# MCU.net
KiCad netlist of a schematic drawn in Altium Designer
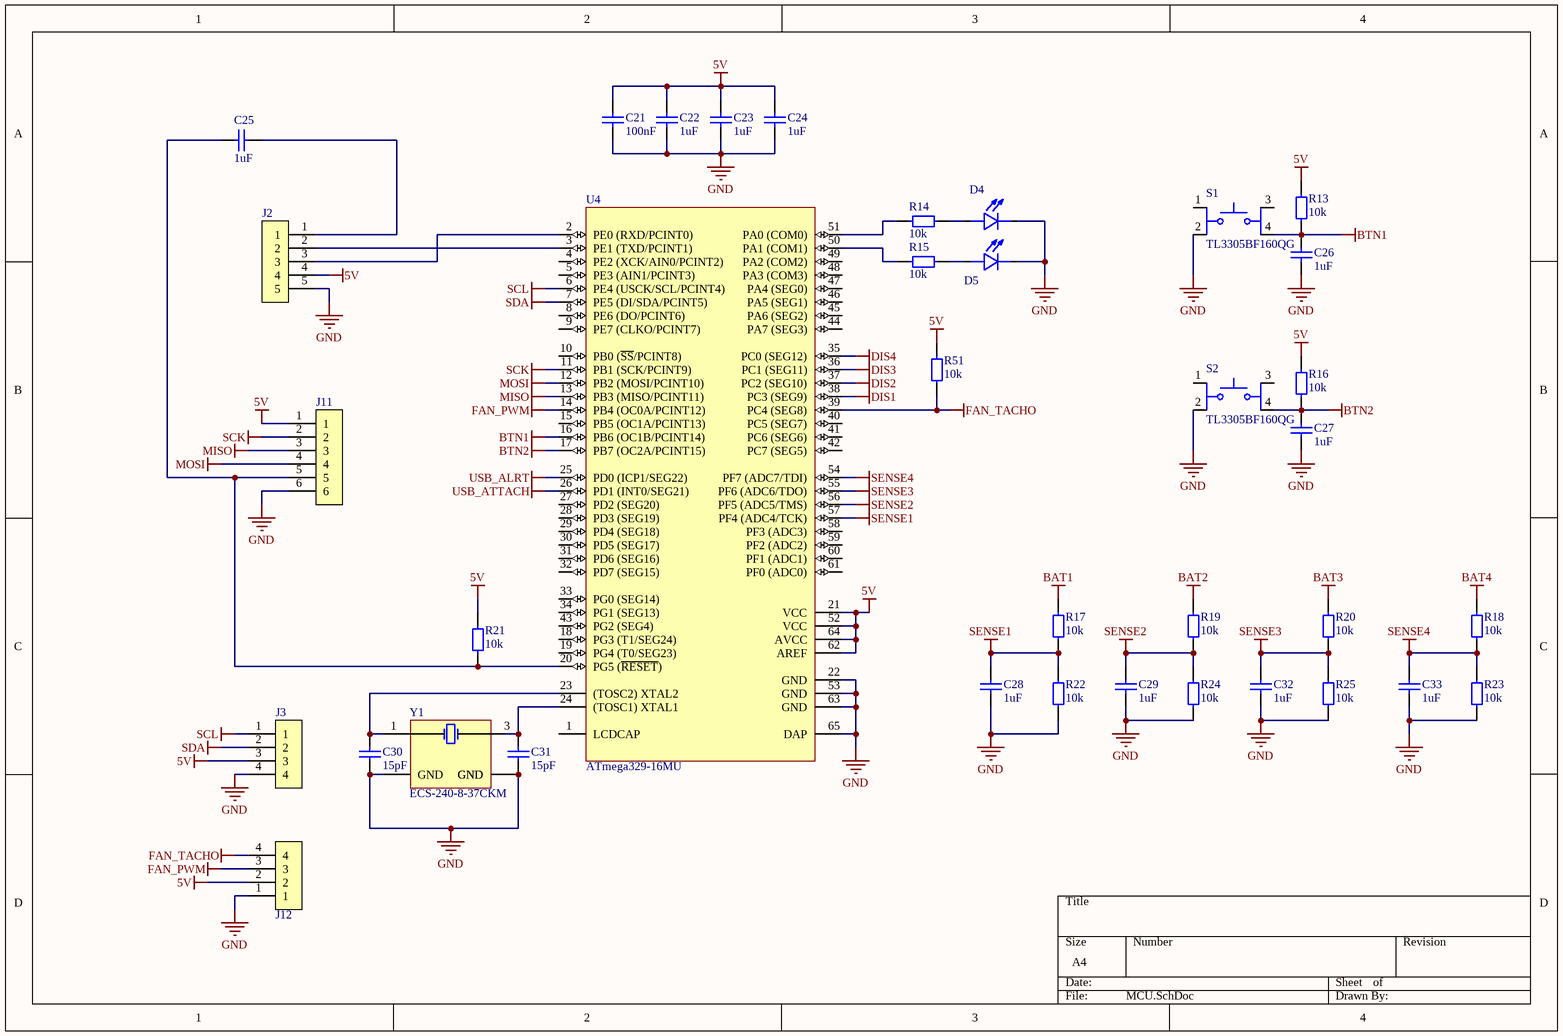
[diagram p0: MCU.SchDoc]

(export (version "E")
  (design (tool "Eeschema 10.0.6"))
  (components
    (comp (ref "C21")
      (value "100nF")
      (footprint "0603 Capacitor")
      (description "100nF 50V 0603")
      (libsource (lib "Capacitor") (part "Capacitor 100nF 0603"))
    )
    (comp (ref "C22")
      (value "1uF")
      (footprint "0603 Capacitor")
      (description "1uF 50V 0603")
      (libsource (lib "Capacitor") (part "Capacitor 1uF 0603"))
    )
    (comp (ref "C23")
      (value "1uF")
      (footprint "0603 Capacitor")
      (description "1uF 50V 0603")
      (libsource (lib "Capacitor") (part "Capacitor 1uF 0603"))
    )
    (comp (ref "C24")
      (value "1uF")
      (footprint "0603 Capacitor")
      (description "1uF 50V 0603")
      (libsource (lib "Capacitor") (part "Capacitor 1uF 0603"))
    )
    (comp (ref "C25")
      (value "1uF")
      (footprint "0603 Capacitor")
      (description "1uF 50V 0603")
      (libsource (lib "Capacitor") (part "Capacitor 1uF 0603"))
    )
    (comp (ref "C26")
      (value "1uF")
      (footprint "0603 Capacitor")
      (description "1uF 50V 0603")
      (libsource (lib "Capacitor") (part "Capacitor 1uF 0603"))
    )
    (comp (ref "C27")
      (value "1uF")
      (footprint "0603 Capacitor")
      (description "1uF 50V 0603")
      (libsource (lib "Capacitor") (part "Capacitor 1uF 0603"))
    )
    (comp (ref "C28")
      (value "1uF")
      (footprint "0603 Capacitor")
      (description "1uF 50V 0603")
      (libsource (lib "Capacitor") (part "Capacitor 1uF 0603"))
    )
    (comp (ref "C29")
      (value "1uF")
      (footprint "0603 Capacitor")
      (description "1uF 50V 0603")
      (libsource (lib "Capacitor") (part "Capacitor 1uF 0603"))
    )
    (comp (ref "C30")
      (value "15pF")
      (footprint "0603 Capacitor")
      (description "15pF 50V 0603")
      (fields (field (name "MP") "KAM15AR71H103MT"))
      (libsource (lib "Capacitor") (part "Capacitor 15pF 0603"))
    )
    (comp (ref "C31")
      (value "15pF")
      (footprint "0603 Capacitor")
      (description "15pF 50V 0603")
      (fields (field (name "MP") "KAM15AR71H103MT"))
      (libsource (lib "Capacitor") (part "Capacitor 15pF 0603"))
    )
    (comp (ref "C32")
      (value "1uF")
      (footprint "0603 Capacitor")
      (description "1uF 50V 0603")
      (libsource (lib "Capacitor") (part "Capacitor 1uF 0603"))
    )
    (comp (ref "C33")
      (value "1uF")
      (footprint "0603 Capacitor")
      (description "1uF 50V 0603")
      (libsource (lib "Capacitor") (part "Capacitor 1uF 0603"))
    )
    (comp (ref "D4")
      (value "LTST-C190KGKT")
      (footprint "LED 0603")
      (description "1.6x0.8mm Smd Chip Led Lamp")
      (fields (field (name "MF") "Kingbright") (field (name "MP") "KPT-1608ZGC"))
      (libsource (lib "LED") (part "LED 0603"))
    )
    (comp (ref "D5")
      (value "LTST-C190KGKT")
      (footprint "LED 0603")
      (description "1.6x0.8mm Smd Chip Led Lamp")
      (fields (field (name "MF") "Kingbright") (field (name "MP") "KPT-1608ZGC"))
      (libsource (lib "LED") (part "LED 0603"))
    )
    (comp (ref "J2")
      (value "5-534237-3")
      (footprint "5pin header")
      (description "2.54mm")
      (fields (field (name "MF") "{'manufacturer': 'TE Connectivity'}") (field (name "MP") "534237-4"))
      (libsource (lib "Connector") (part "5pin 2.54 SAMTEC"))
    )
    (comp (ref "J3")
      (value "MTSW-104-07-G-S-000")
      (footprint "HDRV4W64P0X254_1X4_1016X254X864P")
      (description "CONN HEADER VERT 4POS 2.54MM")
      (libsource (lib "") (part "4 pin header_1"))
    )
    (comp (ref "J11")
      (value "MTSW-106-07-L-S-210")
      (footprint "SAMTEC_MTSW-106-23-L-S-240")
      (description "CONN HEADER VERT 6POS 2.54MM")
      (fields
        (field (name "MANUFACTURER_PART_NUMBER") "MTSW-104-07-G-S-000")
        (field (name "MP") "4 pin header")
      )
      (libsource (lib "Connector") (part "6 pin header"))
    )
    (comp (ref "J12")
      (value "MTSW-104-07-G-S-000")
      (footprint "HDRV4W64P0X254_1X4_1016X254X864P")
      (description "CONN HEADER VERT 4POS 2.54MM")
      (fields (field (name "MP") "4 pin header"))
      (libsource (lib "Connector") (part "4 pin header"))
    )
    (comp (ref "R13")
      (value "10k")
      (footprint "0603 Resistor")
      (description "10k 0603")
      (libsource (lib "Resistors") (part "Resistor 10k 0603"))
    )
    (comp (ref "R14")
      (value "10k")
      (footprint "0603 Resistor")
      (description "10k 0603")
      (libsource (lib "Resistors") (part "Resistor 10k 0603"))
    )
    (comp (ref "R15")
      (value "10k")
      (footprint "0603 Resistor")
      (description "10k 0603")
      (libsource (lib "Resistors") (part "Resistor 10k 0603"))
    )
    (comp (ref "R16")
      (value "10k")
      (footprint "0603 Resistor")
      (description "10k 0603")
      (libsource (lib "Resistors") (part "Resistor 10k 0603"))
    )
    (comp (ref "R17")
      (value "10k")
      (footprint "0603 Resistor")
      (description "10k 0603")
      (libsource (lib "Resistors") (part "Resistor 10k 0603"))
    )
    (comp (ref "R18")
      (value "10k")
      (footprint "0603 Resistor")
      (description "10k 0603")
      (libsource (lib "Resistors") (part "Resistor 10k 0603"))
    )
    (comp (ref "R19")
      (value "10k")
      (footprint "0603 Resistor")
      (description "10k 0603")
      (libsource (lib "Resistors") (part "Resistor 10k 0603"))
    )
    (comp (ref "R20")
      (value "10k")
      (footprint "0603 Resistor")
      (description "10k 0603")
      (libsource (lib "Resistors") (part "Resistor 10k 0603"))
    )
    (comp (ref "R21")
      (value "10k")
      (footprint "0603 Resistor")
      (description "10k 0603")
      (libsource (lib "Resistors") (part "Resistor 10k 0603"))
    )
    (comp (ref "R22")
      (value "10k")
      (footprint "0603 Resistor")
      (description "10k 0603")
      (libsource (lib "Resistors") (part "Resistor 10k 0603"))
    )
    (comp (ref "R23")
      (value "10k")
      (footprint "0603 Resistor")
      (description "10k 0603")
      (libsource (lib "Resistors") (part "Resistor 10k 0603"))
    )
    (comp (ref "R24")
      (value "10k")
      (footprint "0603 Resistor")
      (description "10k 0603")
      (libsource (lib "Resistors") (part "Resistor 10k 0603"))
    )
    (comp (ref "R25")
      (value "10k")
      (footprint "0603 Resistor")
      (description "10k 0603")
      (libsource (lib "Resistors") (part "Resistor 10k 0603"))
    )
    (comp (ref "R51")
      (value "10k")
      (footprint "0603 Resistor")
      (description "10k 0603")
      (libsource (lib "Resistors") (part "Resistor 10k 0603"))
    )
    (comp (ref "S1")
      (value "TL3305BF160QG")
      (footprint "SW_TL3305BF160QG")
      (description "Tactile Switch SPST-NO Top Actuated Surface Mount")
      (fields (field (name "MF") "E-Switch"))
      (libsource (lib "Switches") (part "TL3305BF160QG"))
    )
    (comp (ref "S2")
      (value "TL3305BF160QG")
      (footprint "SW_TL3305BF160QG")
      (description "Tactile Switch SPST-NO Top Actuated Surface Mount")
      (fields (field (name "MF") "E-Switch"))
      (libsource (lib "Switches") (part "TL3305BF160QG"))
    )
    (comp (ref "U4")
      (value "ATmega329-16MU")
      (footprint "ATmega329")
      (libsource (lib "DCDC") (part "ATmega329-16MU"))
    )
    (comp (ref "Y1")
      (value "ECS-240-8-37CKM")
      (footprint "IC:XTAL_ECS-240-8-37CKM")
      (libsource (lib "Crystal") (part "ECS-240-8-37CKM"))
    )
  )
  (nets
    (net (code "1") (name "5V") (class "Default")
      (node (ref "C21") (pin "2") (pinfunction "2_2") (pintype "passive"))
      (node (ref "C22") (pin "2") (pinfunction "2_2") (pintype "passive"))
      (node (ref "C23") (pin "2") (pinfunction "2_2") (pintype "passive"))
      (node (ref "C24") (pin "2") (pinfunction "2_2") (pintype "passive"))
      (node (ref "J11") (pin "1") (pinfunction "1_1") (pintype "passive"))
      (node (ref "J12") (pin "2") (pinfunction "2_2") (pintype "passive"))
      (node (ref "J2") (pin "4") (pinfunction "4_4") (pintype "passive"))
      (node (ref "J3") (pin "3") (pinfunction "3_3") (pintype "passive"))
      (node (ref "R13") (pin "1") (pinfunction "CCW_1") (pintype "passive"))
      (node (ref "R16") (pin "1") (pinfunction "CCW_1") (pintype "passive"))
      (node (ref "R21") (pin "1") (pinfunction "CCW_1") (pintype "passive"))
      (node (ref "R51") (pin "2") (pinfunction "CW_2") (pintype "passive"))
      (node (ref "U4") (pin "21") (pinfunction "VCC_21") (pintype "power_in"))
      (node (ref "U4") (pin "52") (pinfunction "VCC_52") (pintype "power_in"))
      (node (ref "U4") (pin "62") (pinfunction "AREF_62") (pintype "passive"))
      (node (ref "U4") (pin "64") (pinfunction "AVCC_64") (pintype "power_in"))
    )
    (net (code "2") (name "BAT1") (class "Default")
      (node (ref "R17") (pin "1") (pinfunction "CCW_1") (pintype "passive"))
    )
    (net (code "3") (name "BAT2") (class "Default")
      (node (ref "R19") (pin "1") (pinfunction "CCW_1") (pintype "passive"))
    )
    (net (code "4") (name "BAT3") (class "Default")
      (node (ref "R20") (pin "1") (pinfunction "CCW_1") (pintype "passive"))
    )
    (net (code "5") (name "BAT4") (class "Default")
      (node (ref "R18") (pin "1") (pinfunction "CCW_1") (pintype "passive"))
    )
    (net (code "6") (name "BTN1") (class "Default")
      (node (ref "C26") (pin "2") (pinfunction "2_2") (pintype "passive"))
      (node (ref "R13") (pin "2") (pinfunction "CW_2") (pintype "passive"))
      (node (ref "S1") (pin "4") (pinfunction "4_4") (pintype "passive"))
      (node (ref "U4") (pin "16") (pinfunction "PB6_(OC1B/PCINT14)_16") (pintype "bidirectional"))
    )
    (net (code "7") (name "BTN2") (class "Default")
      (node (ref "C27") (pin "2") (pinfunction "2_2") (pintype "passive"))
      (node (ref "R16") (pin "2") (pinfunction "CW_2") (pintype "passive"))
      (node (ref "S2") (pin "4") (pinfunction "4_4") (pintype "passive"))
      (node (ref "U4") (pin "17") (pinfunction "PB7_(OC2A/PCINT15)_17") (pintype "bidirectional"))
    )
    (net (code "8") (name "DIS1") (class "Default")
      (node (ref "U4") (pin "38") (pinfunction "PC3_(SEG9)_38") (pintype "bidirectional"))
    )
    (net (code "9") (name "DIS2") (class "Default")
      (node (ref "U4") (pin "37") (pinfunction "PC2_(SEG10)_37") (pintype "bidirectional"))
    )
    (net (code "10") (name "DIS3") (class "Default")
      (node (ref "U4") (pin "36") (pinfunction "PC1_(SEG11)_36") (pintype "bidirectional"))
    )
    (net (code "11") (name "DIS4") (class "Default")
      (node (ref "U4") (pin "35") (pinfunction "PC0_(SEG12)_35") (pintype "bidirectional"))
    )
    (net (code "12") (name "FAN_PWM") (class "Default")
      (node (ref "J12") (pin "3") (pinfunction "3_3") (pintype "passive"))
      (node (ref "U4") (pin "14") (pinfunction "PB4_(OC0A/PCINT12)_14") (pintype "bidirectional"))
    )
    (net (code "13") (name "FAN_TACHO") (class "Default")
      (node (ref "J12") (pin "4") (pinfunction "4_4") (pintype "passive"))
      (node (ref "R51") (pin "1") (pinfunction "CCW_1") (pintype "passive"))
      (node (ref "U4") (pin "39") (pinfunction "PC4_(SEG8)_39") (pintype "bidirectional"))
    )
    (net (code "14") (name "GND") (class "Default")
      (node (ref "C21") (pin "1") (pinfunction "1_1") (pintype "passive"))
      (node (ref "C22") (pin "1") (pinfunction "1_1") (pintype "passive"))
      (node (ref "C23") (pin "1") (pinfunction "1_1") (pintype "passive"))
      (node (ref "C24") (pin "1") (pinfunction "1_1") (pintype "passive"))
      (node (ref "C26") (pin "1") (pinfunction "1_1") (pintype "passive"))
      (node (ref "C27") (pin "1") (pinfunction "1_1") (pintype "passive"))
      (node (ref "C28") (pin "1") (pinfunction "1_1") (pintype "passive"))
      (node (ref "C29") (pin "1") (pinfunction "1_1") (pintype "passive"))
      (node (ref "C30") (pin "1") (pinfunction "1_1") (pintype "passive"))
      (node (ref "C31") (pin "1") (pinfunction "1_1") (pintype "passive"))
      (node (ref "C32") (pin "1") (pinfunction "1_1") (pintype "passive"))
      (node (ref "C33") (pin "1") (pinfunction "1_1") (pintype "passive"))
      (node (ref "D4") (pin "2") (pinfunction "C_2") (pintype "passive"))
      (node (ref "D5") (pin "2") (pinfunction "C_2") (pintype "passive"))
      (node (ref "J11") (pin "6") (pinfunction "6_6") (pintype "passive"))
      (node (ref "J12") (pin "1") (pinfunction "1_1") (pintype "passive"))
      (node (ref "J2") (pin "5") (pinfunction "5_5") (pintype "passive"))
      (node (ref "J3") (pin "4") (pinfunction "4_4") (pintype "passive"))
      (node (ref "R22") (pin "2") (pinfunction "CW_2") (pintype "passive"))
      (node (ref "R23") (pin "2") (pinfunction "CW_2") (pintype "passive"))
      (node (ref "R24") (pin "2") (pinfunction "CW_2") (pintype "passive"))
      (node (ref "R25") (pin "2") (pinfunction "CW_2") (pintype "passive"))
      (node (ref "S1") (pin "2") (pinfunction "2_2") (pintype "passive"))
      (node (ref "S2") (pin "2") (pinfunction "2_2") (pintype "passive"))
      (node (ref "U4") (pin "22") (pinfunction "GND_22") (pintype "power_in"))
      (node (ref "U4") (pin "53") (pinfunction "GND_53") (pintype "power_in"))
      (node (ref "U4") (pin "63") (pinfunction "GND_63") (pintype "power_in"))
      (node (ref "U4") (pin "65") (pinfunction "DAP_65") (pintype "power_in"))
      (node (ref "Y1") (pin "2") (pinfunction "GND_2") (pintype "passive"))
      (node (ref "Y1") (pin "4") (pinfunction "GND_4") (pintype "passive"))
    )
    (net (code "15") (name "MISO") (class "Default")
      (node (ref "J11") (pin "3") (pinfunction "3_3") (pintype "passive"))
      (node (ref "U4") (pin "13") (pinfunction "PB3_(MISO/PCINT11)_13") (pintype "bidirectional"))
    )
    (net (code "16") (name "MOSI") (class "Default")
      (node (ref "J11") (pin "4") (pinfunction "4_4") (pintype "passive"))
      (node (ref "U4") (pin "12") (pinfunction "PB2_(MOSI/PCINT10)_12") (pintype "bidirectional"))
    )
    (net (code "17") (name "Net-(C25-Pad1)") (class "Default")
      (node (ref "C25") (pin "1") (pinfunction "1_1") (pintype "passive"))
      (node (ref "J2") (pin "1") (pinfunction "1_1") (pintype "passive"))
    )
    (net (code "18") (name "Net-(D4-A)") (class "Default")
      (node (ref "D4") (pin "1") (pinfunction "A_1") (pintype "passive"))
      (node (ref "R14") (pin "1") (pinfunction "CCW_1") (pintype "passive"))
    )
    (net (code "19") (name "Net-(D5-A)") (class "Default")
      (node (ref "D5") (pin "1") (pinfunction "A_1") (pintype "passive"))
      (node (ref "R15") (pin "1") (pinfunction "CCW_1") (pintype "passive"))
    )
    (net (code "20") (name "Net-(R14-CW)") (class "Default")
      (node (ref "R14") (pin "2") (pinfunction "CW_2") (pintype "passive"))
      (node (ref "U4") (pin "51") (pinfunction "PA0_(COM0)_51") (pintype "bidirectional"))
    )
    (net (code "21") (name "Net-(R15-CW)") (class "Default")
      (node (ref "R15") (pin "2") (pinfunction "CW_2") (pintype "passive"))
      (node (ref "U4") (pin "50") (pinfunction "PA1_(COM1)_50") (pintype "bidirectional"))
    )
    (net (code "22") (name "Net-(R21-CW)") (class "Default")
      (node (ref "C25") (pin "2") (pinfunction "2_2") (pintype "passive"))
      (node (ref "J11") (pin "5") (pinfunction "5_5") (pintype "passive"))
      (node (ref "R21") (pin "2") (pinfunction "CW_2") (pintype "passive"))
      (node (ref "U4") (pin "20") (pinfunction "PG5_(~{RESET})_20") (pintype "bidirectional"))
    )
    (net (code "23") (name "Net-(U4-(TOSC1)_XTAL1)") (class "Default")
      (node (ref "C31") (pin "2") (pinfunction "2_2") (pintype "passive"))
      (node (ref "U4") (pin "24") (pinfunction "(TOSC1)_XTAL1_24") (pintype "passive"))
      (node (ref "Y1") (pin "3") (pinfunction "X2_3") (pintype "passive"))
    )
    (net (code "24") (name "Net-(U4-(TOSC2)_XTAL2)") (class "Default")
      (node (ref "C30") (pin "2") (pinfunction "2_2") (pintype "passive"))
      (node (ref "U4") (pin "23") (pinfunction "(TOSC2)_XTAL2_23") (pintype "passive"))
      (node (ref "Y1") (pin "1") (pinfunction "X1_1") (pintype "passive"))
    )
    (net (code "25") (name "Net-(U4-PE0_(RXD{slash}PCINT0))") (class "Default")
      (node (ref "J2") (pin "3") (pinfunction "3_3") (pintype "passive"))
      (node (ref "U4") (pin "2") (pinfunction "PE0_(RXD/PCINT0)_2") (pintype "bidirectional"))
    )
    (net (code "26") (name "Net-(U4-PE1_(TXD{slash}PCINT1))") (class "Default")
      (node (ref "J2") (pin "2") (pinfunction "2_2") (pintype "passive"))
      (node (ref "U4") (pin "3") (pinfunction "PE1_(TXD/PCINT1)_3") (pintype "bidirectional"))
    )
    (net (code "27") (name "SCK") (class "Default")
      (node (ref "J11") (pin "2") (pinfunction "2_2") (pintype "passive"))
      (node (ref "U4") (pin "11") (pinfunction "PB1_(SCK/PCINT9)_11") (pintype "bidirectional"))
    )
    (net (code "28") (name "SCL") (class "Default")
      (node (ref "J3") (pin "1") (pinfunction "1_1") (pintype "passive"))
      (node (ref "U4") (pin "6") (pinfunction "PE4_(USCK/SCL/PCINT4)_6") (pintype "bidirectional"))
    )
    (net (code "29") (name "SDA") (class "Default")
      (node (ref "J3") (pin "2") (pinfunction "2_2") (pintype "passive"))
      (node (ref "U4") (pin "7") (pinfunction "PE5_(DI/SDA/PCINT5)_7") (pintype "bidirectional"))
    )
    (net (code "30") (name "SENSE1") (class "Default")
      (node (ref "C28") (pin "2") (pinfunction "2_2") (pintype "passive"))
      (node (ref "R17") (pin "2") (pinfunction "CW_2") (pintype "passive"))
      (node (ref "R22") (pin "1") (pinfunction "CCW_1") (pintype "passive"))
      (node (ref "U4") (pin "57") (pinfunction "PF4_(ADC4/TCK)_57") (pintype "bidirectional"))
    )
    (net (code "31") (name "SENSE2") (class "Default")
      (node (ref "C29") (pin "2") (pinfunction "2_2") (pintype "passive"))
      (node (ref "R19") (pin "2") (pinfunction "CW_2") (pintype "passive"))
      (node (ref "R24") (pin "1") (pinfunction "CCW_1") (pintype "passive"))
      (node (ref "U4") (pin "56") (pinfunction "PF5_(ADC5/TMS)_56") (pintype "bidirectional"))
    )
    (net (code "32") (name "SENSE3") (class "Default")
      (node (ref "C32") (pin "2") (pinfunction "2_2") (pintype "passive"))
      (node (ref "R20") (pin "2") (pinfunction "CW_2") (pintype "passive"))
      (node (ref "R25") (pin "1") (pinfunction "CCW_1") (pintype "passive"))
      (node (ref "U4") (pin "55") (pinfunction "PF6_(ADC6/TDO)_55") (pintype "bidirectional"))
    )
    (net (code "33") (name "SENSE4") (class "Default")
      (node (ref "C33") (pin "2") (pinfunction "2_2") (pintype "passive"))
      (node (ref "R18") (pin "2") (pinfunction "CW_2") (pintype "passive"))
      (node (ref "R23") (pin "1") (pinfunction "CCW_1") (pintype "passive"))
      (node (ref "U4") (pin "54") (pinfunction "PF7_(ADC7/TDI)_54") (pintype "bidirectional"))
    )
    (net (code "34") (name "USB_ALRT") (class "Default")
      (node (ref "U4") (pin "25") (pinfunction "PD0_(ICP1/SEG22)_25") (pintype "bidirectional"))
    )
    (net (code "35") (name "USB_ATTACH") (class "Default")
      (node (ref "U4") (pin "26") (pinfunction "PD1_(INT0/SEG21)_26") (pintype "bidirectional"))
    )
    (net (code "36") (name "unconnected-(S1-Pad1)") (class "Default")
      (node (ref "S1") (pin "1") (pinfunction "1_1") (pintype "passive"))
    )
    (net (code "37") (name "unconnected-(S1-Pad3)") (class "Default")
      (node (ref "S1") (pin "3") (pinfunction "3_3") (pintype "passive"))
    )
    (net (code "38") (name "unconnected-(S2-Pad1)") (class "Default")
      (node (ref "S2") (pin "1") (pinfunction "1_1") (pintype "passive"))
    )
    (net (code "39") (name "unconnected-(S2-Pad3)") (class "Default")
      (node (ref "S2") (pin "3") (pinfunction "3_3") (pintype "passive"))
    )
    (net (code "40") (name "unconnected-(U4-LCDCAP-Pad1)") (class "Default")
      (node (ref "U4") (pin "1") (pinfunction "LCDCAP_1") (pintype "passive"))
    )
    (net (code "41") (name "unconnected-(U4-PA2_(COM2)-Pad49)") (class "Default")
      (node (ref "U4") (pin "49") (pinfunction "PA2_(COM2)_49") (pintype "bidirectional"))
    )
    (net (code "42") (name "unconnected-(U4-PA3_(COM3)-Pad48)") (class "Default")
      (node (ref "U4") (pin "48") (pinfunction "PA3_(COM3)_48") (pintype "bidirectional"))
    )
    (net (code "43") (name "unconnected-(U4-PA4_(SEG0)-Pad47)") (class "Default")
      (node (ref "U4") (pin "47") (pinfunction "PA4_(SEG0)_47") (pintype "bidirectional"))
    )
    (net (code "44") (name "unconnected-(U4-PA5_(SEG1)-Pad46)") (class "Default")
      (node (ref "U4") (pin "46") (pinfunction "PA5_(SEG1)_46") (pintype "bidirectional"))
    )
    (net (code "45") (name "unconnected-(U4-PA6_(SEG2)-Pad45)") (class "Default")
      (node (ref "U4") (pin "45") (pinfunction "PA6_(SEG2)_45") (pintype "bidirectional"))
    )
    (net (code "46") (name "unconnected-(U4-PA7_(SEG3)-Pad44)") (class "Default")
      (node (ref "U4") (pin "44") (pinfunction "PA7_(SEG3)_44") (pintype "bidirectional"))
    )
    (net (code "47") (name "unconnected-(U4-PB0_(~{SS}{slash}PCINT8)-Pad10)") (class "Default")
      (node (ref "U4") (pin "10") (pinfunction "PB0_(~{SS}/PCINT8)_10") (pintype "bidirectional"))
    )
    (net (code "48") (name "unconnected-(U4-PB5_(OC1A{slash}PCINT13)-Pad15)") (class "Default")
      (node (ref "U4") (pin "15") (pinfunction "PB5_(OC1A/PCINT13)_15") (pintype "bidirectional"))
    )
    (net (code "49") (name "unconnected-(U4-PC5_(SEG7)-Pad40)") (class "Default")
      (node (ref "U4") (pin "40") (pinfunction "PC5_(SEG7)_40") (pintype "bidirectional"))
    )
    (net (code "50") (name "unconnected-(U4-PC6_(SEG6)-Pad41)") (class "Default")
      (node (ref "U4") (pin "41") (pinfunction "PC6_(SEG6)_41") (pintype "bidirectional"))
    )
    (net (code "51") (name "unconnected-(U4-PC7_(SEG5)-Pad42)") (class "Default")
      (node (ref "U4") (pin "42") (pinfunction "PC7_(SEG5)_42") (pintype "bidirectional"))
    )
    (net (code "52") (name "unconnected-(U4-PD2_(SEG20)-Pad27)") (class "Default")
      (node (ref "U4") (pin "27") (pinfunction "PD2_(SEG20)_27") (pintype "bidirectional"))
    )
    (net (code "53") (name "unconnected-(U4-PD3_(SEG19)-Pad28)") (class "Default")
      (node (ref "U4") (pin "28") (pinfunction "PD3_(SEG19)_28") (pintype "bidirectional"))
    )
    (net (code "54") (name "unconnected-(U4-PD4_(SEG18)-Pad29)") (class "Default")
      (node (ref "U4") (pin "29") (pinfunction "PD4_(SEG18)_29") (pintype "bidirectional"))
    )
    (net (code "55") (name "unconnected-(U4-PD5_(SEG17)-Pad30)") (class "Default")
      (node (ref "U4") (pin "30") (pinfunction "PD5_(SEG17)_30") (pintype "bidirectional"))
    )
    (net (code "56") (name "unconnected-(U4-PD6_(SEG16)-Pad31)") (class "Default")
      (node (ref "U4") (pin "31") (pinfunction "PD6_(SEG16)_31") (pintype "bidirectional"))
    )
    (net (code "57") (name "unconnected-(U4-PD7_(SEG15)-Pad32)") (class "Default")
      (node (ref "U4") (pin "32") (pinfunction "PD7_(SEG15)_32") (pintype "bidirectional"))
    )
    (net (code "58") (name "unconnected-(U4-PE2_(XCK{slash}AIN0{slash}PCINT2)-Pad4)") (class "Default")
      (node (ref "U4") (pin "4") (pinfunction "PE2_(XCK/AIN0/PCINT2)_4") (pintype "bidirectional"))
    )
    (net (code "59") (name "unconnected-(U4-PE3_(AIN1{slash}PCINT3)-Pad5)") (class "Default")
      (node (ref "U4") (pin "5") (pinfunction "PE3_(AIN1/PCINT3)_5") (pintype "bidirectional"))
    )
    (net (code "60") (name "unconnected-(U4-PE6_(DO{slash}PCINT6)-Pad8)") (class "Default")
      (node (ref "U4") (pin "8") (pinfunction "PE6_(DO/PCINT6)_8") (pintype "bidirectional"))
    )
    (net (code "61") (name "unconnected-(U4-PE7_(CLKO{slash}PCINT7)-Pad9)") (class "Default")
      (node (ref "U4") (pin "9") (pinfunction "PE7_(CLKO/PCINT7)_9") (pintype "bidirectional"))
    )
    (net (code "62") (name "unconnected-(U4-PF0_(ADC0)-Pad61)") (class "Default")
      (node (ref "U4") (pin "61") (pinfunction "PF0_(ADC0)_61") (pintype "bidirectional"))
    )
    (net (code "63") (name "unconnected-(U4-PF1_(ADC1)-Pad60)") (class "Default")
      (node (ref "U4") (pin "60") (pinfunction "PF1_(ADC1)_60") (pintype "bidirectional"))
    )
    (net (code "64") (name "unconnected-(U4-PF2_(ADC2)-Pad59)") (class "Default")
      (node (ref "U4") (pin "59") (pinfunction "PF2_(ADC2)_59") (pintype "bidirectional"))
    )
    (net (code "65") (name "unconnected-(U4-PF3_(ADC3)-Pad58)") (class "Default")
      (node (ref "U4") (pin "58") (pinfunction "PF3_(ADC3)_58") (pintype "bidirectional"))
    )
    (net (code "66") (name "unconnected-(U4-PG0_(SEG14)-Pad33)") (class "Default")
      (node (ref "U4") (pin "33") (pinfunction "PG0_(SEG14)_33") (pintype "bidirectional"))
    )
    (net (code "67") (name "unconnected-(U4-PG1_(SEG13)-Pad34)") (class "Default")
      (node (ref "U4") (pin "34") (pinfunction "PG1_(SEG13)_34") (pintype "bidirectional"))
    )
    (net (code "68") (name "unconnected-(U4-PG2_(SEG4)-Pad43)") (class "Default")
      (node (ref "U4") (pin "43") (pinfunction "PG2_(SEG4)_43") (pintype "bidirectional"))
    )
    (net (code "69") (name "unconnected-(U4-PG3_(T1{slash}SEG24)-Pad18)") (class "Default")
      (node (ref "U4") (pin "18") (pinfunction "PG3_(T1/SEG24)_18") (pintype "bidirectional"))
    )
    (net (code "70") (name "unconnected-(U4-PG4_(T0{slash}SEG23)-Pad19)") (class "Default")
      (node (ref "U4") (pin "19") (pinfunction "PG4_(T0/SEG23)_19") (pintype "bidirectional"))
    )
  )
)
